# motor_driver.net
KiCad netlist of a schematic drawn in Altium Designer
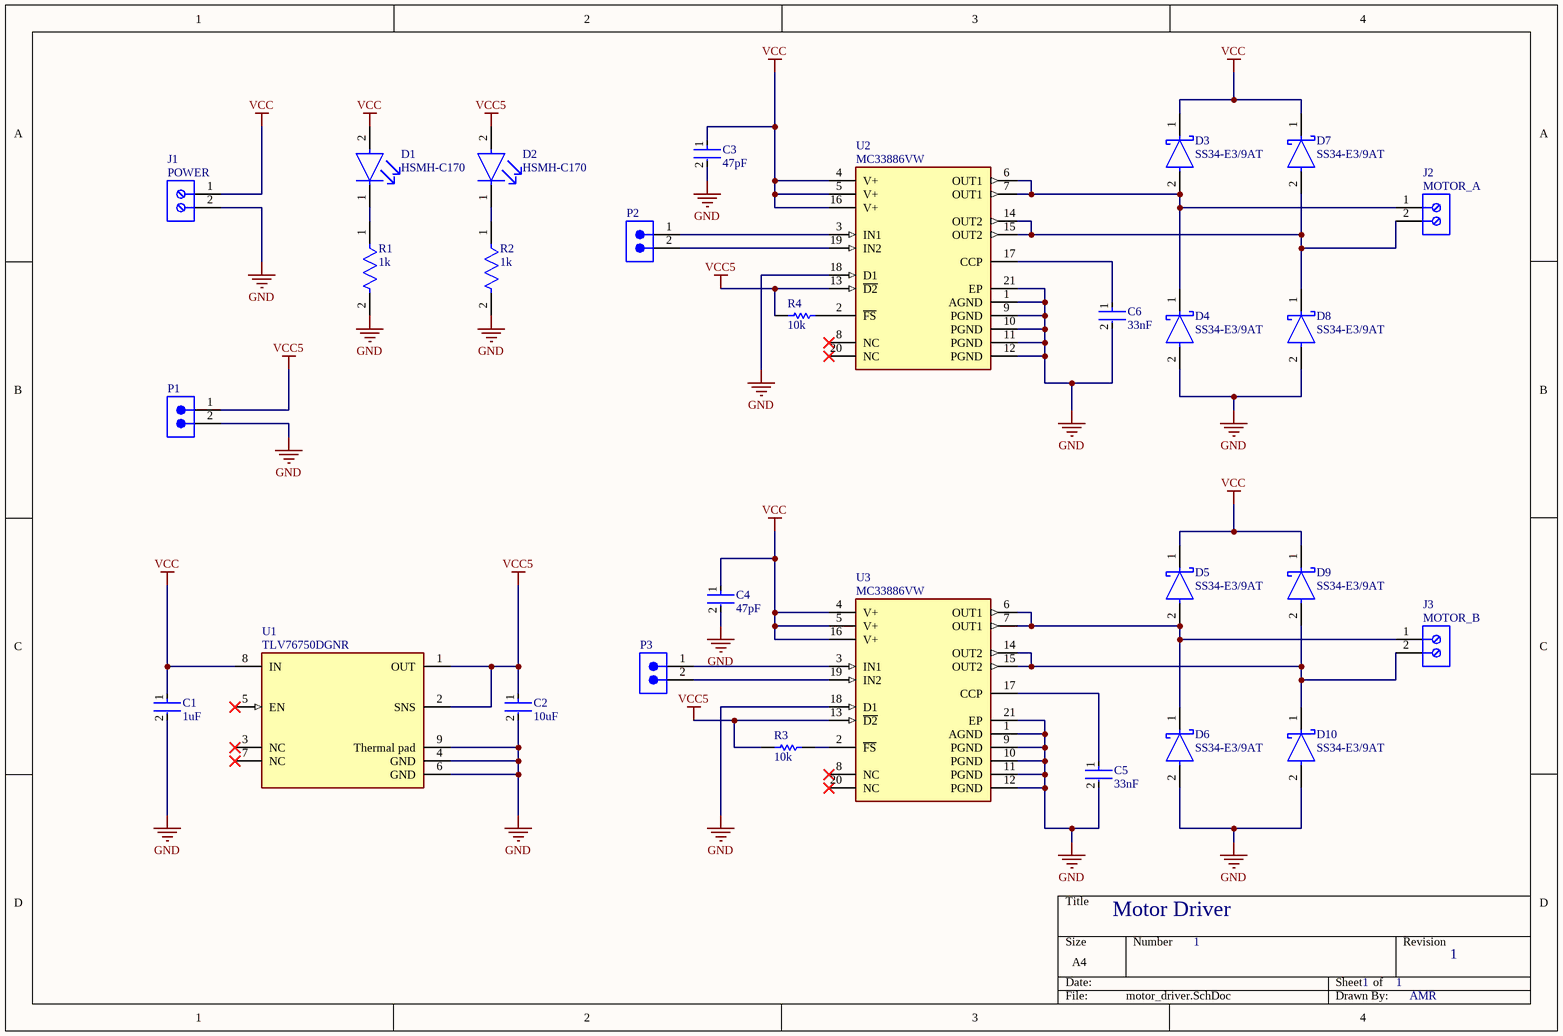
[diagram p0: motor_driver.SchDoc]

(export (version "E")
  (design (tool "Eeschema 10.0.6"))
  (components
    (comp (ref "C1")
      (value "1uF")
      (footprint "FP-CC0603-DA-IPC_A")
      (description "CAP CER 0.1UF 16V X7R 0603")
      (fields
        (field (name "OCTOPART") "https://octopart.com/cc0603krx7r7bb104-yageo-192941")
        (field (name "TOLERANCE") "0.1")
      )
      (libsource (lib "1uF") (part "CMP-2000-05002-2"))
    )
    (comp (ref "C2")
      (value "10uF")
      (footprint "FP-GRM188-0_1-e0_2_0_55-IPC_A")
      (description "Chip Multilayer Ceramic Capacitors for General Purpose, 0603, 10uF, X5R, 15%, 20%, 6.3V")
      (fields (field (name "VOLTAGE") "6.3V") (field (name "TOLERANCE") "20%"))
      (libsource (lib "Altium Content Vault") (part "02cd4be3c70576c341d710602a673aa"))
    )
    (comp (ref "C3")
      (value "47pF")
      (footprint "FP-C0805C-DN-IPC_A")
      (description "CAP CER 47PF 100V 5% NP0 0805")
      (fields
        (field (name "MANUFACTURER") "KEMET")
        (field (name "OCTOPART") "https://octopart.com/c0805c470j1gactu-kemet-9138638")
      )
      (libsource (lib "Altium Content Vault") (part "b4654b650e69147ec39a6b967a45e02"))
    )
    (comp (ref "C4")
      (value "47pF")
      (footprint "FP-C0805C-DN-IPC_A")
      (description "CAP CER 47PF 100V 5% NP0 0805")
      (fields
        (field (name "MANUFACTURER") "KEMET")
        (field (name "OCTOPART") "https://octopart.com/c0805c470j1gactu-kemet-9138638")
      )
      (libsource (lib "Altium Content Vault") (part "b4654b650e69147ec39a6b967a45e02"))
    )
    (comp (ref "C5")
      (value "33nF")
      (footprint "FP-CC0805-0_85-MFG")
      (description "CAP CER 0.033UF 25V X7R 0805")
      (fields
        (field (name "MANUFACTURER PART NUMBER") "CC0805KRX7R8BB333")
        (field (name "MANUFACTURER") "Yageo")
      )
      (libsource (lib "Altium Content Vault") (part "11868f565c42a9108669ba33697ecf6"))
    )
    (comp (ref "C6")
      (value "33nF")
      (footprint "FP-CC0805-0_85-MFG")
      (description "CAP CER 0.033UF 25V X7R 0805")
      (fields
        (field (name "MANUFACTURER PART NUMBER") "CC0805KRX7R8BB333")
        (field (name "MANUFACTURER") "Yageo")
      )
      (libsource (lib "Altium Content Vault") (part "11868f565c42a9108669ba33697ecf6"))
    )
    (comp (ref "D1")
      (value "HSMH-C170")
      (footprint "FP-HSMS-C170-MFG")
      (description "LED RED DIFFUSED CHIP SMD")
      (libsource (lib "Altium Content Vault") (part "8706943c75ba83719d021d2fdc84c58"))
    )
    (comp (ref "D2")
      (value "HSMH-C170")
      (footprint "FP-HSMS-C170-MFG")
      (description "LED RED DIFFUSED CHIP SMD")
      (libsource (lib "Altium Content Vault") (part "8706943c75ba83719d021d2fdc84c58"))
    )
    (comp (ref "D3")
      (value "SS34-E3/9AT")
      (footprint "FP-SMC-MFG")
      (description "DIODE SCHOTTKY 40V 3A DO214AB")
      (libsource (lib "Altium Content Vault") (part "c1678fac7984e62e0809fbf79c06691"))
    )
    (comp (ref "D4")
      (value "SS34-E3/9AT")
      (footprint "FP-SMC-MFG")
      (description "DIODE SCHOTTKY 40V 3A DO214AB")
      (libsource (lib "Altium Content Vault") (part "c1678fac7984e62e0809fbf79c06691"))
    )
    (comp (ref "D5")
      (value "SS34-E3/9AT")
      (footprint "FP-SMC-MFG")
      (description "DIODE SCHOTTKY 40V 3A DO214AB")
      (libsource (lib "Altium Content Vault") (part "c1678fac7984e62e0809fbf79c06691"))
    )
    (comp (ref "D6")
      (value "SS34-E3/9AT")
      (footprint "FP-SMC-MFG")
      (description "DIODE SCHOTTKY 40V 3A DO214AB")
      (libsource (lib "Altium Content Vault") (part "c1678fac7984e62e0809fbf79c06691"))
    )
    (comp (ref "D7")
      (value "SS34-E3/9AT")
      (footprint "FP-SMC-MFG")
      (description "DIODE SCHOTTKY 40V 3A DO214AB")
      (libsource (lib "Altium Content Vault") (part "c1678fac7984e62e0809fbf79c06691"))
    )
    (comp (ref "D8")
      (value "SS34-E3/9AT")
      (footprint "FP-SMC-MFG")
      (description "DIODE SCHOTTKY 40V 3A DO214AB")
      (libsource (lib "Altium Content Vault") (part "c1678fac7984e62e0809fbf79c06691"))
    )
    (comp (ref "D9")
      (value "SS34-E3/9AT")
      (footprint "FP-SMC-MFG")
      (description "DIODE SCHOTTKY 40V 3A DO214AB")
      (libsource (lib "Altium Content Vault") (part "c1678fac7984e62e0809fbf79c06691"))
    )
    (comp (ref "D10")
      (value "SS34-E3/9AT")
      (footprint "FP-SMC-MFG")
      (description "DIODE SCHOTTKY 40V 3A DO214AB")
      (libsource (lib "Altium Content Vault") (part "c1678fac7984e62e0809fbf79c06691"))
    )
    (comp (ref "J1")
      (value "POWER")
      (footprint "691103110002")
      (fields (field (name "VOLTAGE") "125V"))
      (libsource (lib "Altium Content Vault") (part "TBL - 1R - 02P - Screw"))
    )
    (comp (ref "J2")
      (value "MOTOR_A")
      (footprint "691103110002")
      (fields (field (name "VOLTAGE") "125V"))
      (libsource (lib "Altium Content Vault") (part "TBL - 1R - 02P - Screw"))
    )
    (comp (ref "J3")
      (value "MOTOR_B")
      (footprint "691103110002")
      (fields (field (name "VOLTAGE") "125V"))
      (libsource (lib "Altium Content Vault") (part "TBL - 1R - 02P - Screw"))
    )
    (comp (ref "P1")
      (value "61300211121")
      (footprint "61300211121")
      (libsource (lib "Altium Content Vault") (part "Header_Male_1R_02P"))
    )
    (comp (ref "P2")
      (value "61300211121")
      (footprint "61300211121")
      (libsource (lib "Altium Content Vault") (part "Header_Male_1R_02P"))
    )
    (comp (ref "P3")
      (value "61300211121")
      (footprint "61300211121")
      (libsource (lib "Altium Content Vault") (part "Header_Male_1R_02P"))
    )
    (comp (ref "R1")
      (value "1k")
      (footprint "FP-RC0603-0_55-IPC_B")
      (description "RES 1K OHM 1% 1/10W 0603")
      (fields (field (name "TOLERANCE") "1%"))
      (libsource (lib "Components - 03.07.23 - 14.28") (part "CMP-1659-00009-5"))
    )
    (comp (ref "R2")
      (value "1k")
      (footprint "FP-RC0603-0_55-IPC_B")
      (description "RES 1K OHM 1% 1/10W 0603")
      (fields (field (name "TOLERANCE") "1%"))
      (libsource (lib "Components - 03.07.23 - 14.28") (part "CMP-1659-00009-5"))
    )
    (comp (ref "R3")
      (value "10k")
      (footprint "RESC1609X50X30ML8T20")
      (description "Chip Resistor, 10 KOhm, +/- 1%, 100 mW, -55 to 155 degC, 0603 (1608 Metric), RoHS, Tape and Reel")
      (fields (field (name "MANUFACTURER") "Vishay Semiconductor"))
      (libsource (lib "Altium Content Vault") (part "RES-2"))
    )
    (comp (ref "R4")
      (value "10k")
      (footprint "RESC1609X50X30ML8T20")
      (description "Chip Resistor, 10 KOhm, +/- 1%, 100 mW, -55 to 155 degC, 0603 (1608 Metric), RoHS, Tape and Reel")
      (fields (field (name "MANUFACTURER") "Vishay Semiconductor"))
      (libsource (lib "Altium Content Vault") (part "RES-2"))
    )
    (comp (ref "U1")
      (value "TLV76750DGNR")
      (footprint "FP-DGN0008G-IPC_A")
      (libsource (lib "Altium Content Vault") (part "4137fefd6f2351a27154aa09bf60b26"))
    )
    (comp (ref "U2")
      (value "MC33886VW")
      (footprint "FP-SOT397-2-IPC_A")
      (description "Motor Driver CMOS Parallel 20-HSOP")
      (libsource (lib "Altium Content Vault") (part "637c7454df18ad6f63f2a5204066dbd"))
    )
    (comp (ref "U3")
      (value "MC33886VW")
      (footprint "FP-SOT397-2-IPC_A")
      (description "Motor Driver CMOS Parallel 20-HSOP")
      (libsource (lib "Altium Content Vault") (part "637c7454df18ad6f63f2a5204066dbd"))
    )
  )
  (nets
    (net (code "1") (name "GND") (class "Default")
      (node (ref "C1") (pin "2") (pinfunction "2_2") (pintype "passive"))
      (node (ref "C2") (pin "2") (pinfunction "2_2") (pintype "passive"))
      (node (ref "C3") (pin "2") (pinfunction "2_2") (pintype "passive"))
      (node (ref "C4") (pin "2") (pinfunction "2_2") (pintype "passive"))
      (node (ref "C5") (pin "2") (pinfunction "2_2") (pintype "passive"))
      (node (ref "C6") (pin "2") (pinfunction "2_2") (pintype "passive"))
      (node (ref "D10") (pin "2") (pinfunction "A_2") (pintype "passive"))
      (node (ref "D4") (pin "2") (pinfunction "A_2") (pintype "passive"))
      (node (ref "D6") (pin "2") (pinfunction "A_2") (pintype "passive"))
      (node (ref "D8") (pin "2") (pinfunction "A_2") (pintype "passive"))
      (node (ref "J1") (pin "2") (pinfunction "2_2") (pintype "passive"))
      (node (ref "P1") (pin "2") (pinfunction "2_2") (pintype "passive"))
      (node (ref "R1") (pin "2") (pinfunction "2_2") (pintype "passive"))
      (node (ref "R2") (pin "2") (pinfunction "2_2") (pintype "passive"))
      (node (ref "U1") (pin "4") (pinfunction "GND_4") (pintype "power_in"))
      (node (ref "U1") (pin "6") (pinfunction "GND_6") (pintype "power_in"))
      (node (ref "U1") (pin "9") (pinfunction "Thermal_pad_9") (pintype "power_in"))
      (node (ref "U2") (pin "1") (pinfunction "AGND_1") (pintype "power_in"))
      (node (ref "U2") (pin "10") (pinfunction "PGND_10") (pintype "power_in"))
      (node (ref "U2") (pin "11") (pinfunction "PGND_11") (pintype "power_in"))
      (node (ref "U2") (pin "12") (pinfunction "PGND_12") (pintype "power_in"))
      (node (ref "U2") (pin "18") (pinfunction "D1_18") (pintype "input"))
      (node (ref "U2") (pin "21") (pinfunction "EP_21") (pintype "passive"))
      (node (ref "U2") (pin "9") (pinfunction "PGND_9") (pintype "power_in"))
      (node (ref "U3") (pin "1") (pinfunction "AGND_1") (pintype "power_in"))
      (node (ref "U3") (pin "10") (pinfunction "PGND_10") (pintype "power_in"))
      (node (ref "U3") (pin "11") (pinfunction "PGND_11") (pintype "power_in"))
      (node (ref "U3") (pin "12") (pinfunction "PGND_12") (pintype "power_in"))
      (node (ref "U3") (pin "18") (pinfunction "D1_18") (pintype "input"))
      (node (ref "U3") (pin "21") (pinfunction "EP_21") (pintype "passive"))
      (node (ref "U3") (pin "9") (pinfunction "PGND_9") (pintype "power_in"))
    )
    (net (code "2") (name "Net-(D1-C)") (class "Default")
      (node (ref "D1") (pin "1") (pinfunction "C_1") (pintype "passive"))
      (node (ref "R1") (pin "1") (pinfunction "1_1") (pintype "passive"))
    )
    (net (code "3") (name "Net-(D2-C)") (class "Default")
      (node (ref "D2") (pin "1") (pinfunction "C_1") (pintype "passive"))
      (node (ref "R2") (pin "1") (pinfunction "1_1") (pintype "passive"))
    )
    (net (code "4") (name "Net-(D3-A)") (class "Default")
      (node (ref "D3") (pin "2") (pinfunction "A_2") (pintype "passive"))
      (node (ref "D4") (pin "1") (pinfunction "C_1") (pintype "passive"))
      (node (ref "J2") (pin "1") (pinfunction "1_1") (pintype "passive"))
      (node (ref "U2") (pin "6") (pinfunction "OUT1_6") (pintype "output"))
      (node (ref "U2") (pin "7") (pinfunction "OUT1_7") (pintype "output"))
    )
    (net (code "5") (name "Net-(D5-A)") (class "Default")
      (node (ref "D5") (pin "2") (pinfunction "A_2") (pintype "passive"))
      (node (ref "D6") (pin "1") (pinfunction "C_1") (pintype "passive"))
      (node (ref "J3") (pin "1") (pinfunction "1_1") (pintype "passive"))
      (node (ref "U3") (pin "6") (pinfunction "OUT1_6") (pintype "output"))
      (node (ref "U3") (pin "7") (pinfunction "OUT1_7") (pintype "output"))
    )
    (net (code "6") (name "Net-(D7-A)") (class "Default")
      (node (ref "D7") (pin "2") (pinfunction "A_2") (pintype "passive"))
      (node (ref "D8") (pin "1") (pinfunction "C_1") (pintype "passive"))
      (node (ref "J2") (pin "2") (pinfunction "2_2") (pintype "passive"))
      (node (ref "U2") (pin "14") (pinfunction "OUT2_14") (pintype "output"))
      (node (ref "U2") (pin "15") (pinfunction "OUT2_15") (pintype "output"))
    )
    (net (code "7") (name "Net-(D10-C)") (class "Default")
      (node (ref "D10") (pin "1") (pinfunction "C_1") (pintype "passive"))
      (node (ref "D9") (pin "2") (pinfunction "A_2") (pintype "passive"))
      (node (ref "J3") (pin "2") (pinfunction "2_2") (pintype "passive"))
      (node (ref "U3") (pin "14") (pinfunction "OUT2_14") (pintype "output"))
      (node (ref "U3") (pin "15") (pinfunction "OUT2_15") (pintype "output"))
    )
    (net (code "8") (name "Net-(U2-CCP)") (class "Default")
      (node (ref "C6") (pin "1") (pinfunction "1_1") (pintype "passive"))
      (node (ref "U2") (pin "17") (pinfunction "CCP_17") (pintype "passive"))
    )
    (net (code "9") (name "Net-(U2-IN1)") (class "Default")
      (node (ref "P2") (pin "1") (pinfunction "1_1") (pintype "passive"))
      (node (ref "U2") (pin "3") (pinfunction "IN1_3") (pintype "input"))
    )
    (net (code "10") (name "Net-(U2-IN2)") (class "Default")
      (node (ref "P2") (pin "2") (pinfunction "2_2") (pintype "passive"))
      (node (ref "U2") (pin "19") (pinfunction "IN2_19") (pintype "input"))
    )
    (net (code "11") (name "Net-(U2-~{FS})") (class "Default")
      (node (ref "R4") (pin "2") (pinfunction "2_2") (pintype "passive"))
      (node (ref "U2") (pin "2") (pinfunction "~{FS}_2") (pintype "open_collector"))
    )
    (net (code "12") (name "Net-(U3-CCP)") (class "Default")
      (node (ref "C5") (pin "1") (pinfunction "1_1") (pintype "passive"))
      (node (ref "U3") (pin "17") (pinfunction "CCP_17") (pintype "passive"))
    )
    (net (code "13") (name "Net-(U3-IN1)") (class "Default")
      (node (ref "P3") (pin "1") (pinfunction "1_1") (pintype "passive"))
      (node (ref "U3") (pin "3") (pinfunction "IN1_3") (pintype "input"))
    )
    (net (code "14") (name "Net-(U3-IN2)") (class "Default")
      (node (ref "P3") (pin "2") (pinfunction "2_2") (pintype "passive"))
      (node (ref "U3") (pin "19") (pinfunction "IN2_19") (pintype "input"))
    )
    (net (code "15") (name "Net-(U3-~{FS})") (class "Default")
      (node (ref "R3") (pin "2") (pinfunction "2_2") (pintype "passive"))
      (node (ref "U3") (pin "2") (pinfunction "~{FS}_2") (pintype "open_collector"))
    )
    (net (code "16") (name "VCC") (class "Default")
      (node (ref "C1") (pin "1") (pinfunction "1_1") (pintype "passive"))
      (node (ref "C3") (pin "1") (pinfunction "1_1") (pintype "passive"))
      (node (ref "C4") (pin "1") (pinfunction "1_1") (pintype "passive"))
      (node (ref "D1") (pin "2") (pinfunction "A_2") (pintype "passive"))
      (node (ref "D3") (pin "1") (pinfunction "C_1") (pintype "passive"))
      (node (ref "D5") (pin "1") (pinfunction "C_1") (pintype "passive"))
      (node (ref "D7") (pin "1") (pinfunction "C_1") (pintype "passive"))
      (node (ref "D9") (pin "1") (pinfunction "C_1") (pintype "passive"))
      (node (ref "J1") (pin "1") (pinfunction "1_1") (pintype "passive"))
      (node (ref "U1") (pin "8") (pinfunction "IN_8") (pintype "power_in"))
      (node (ref "U2") (pin "16") (pinfunction "V+_16") (pintype "power_in"))
      (node (ref "U2") (pin "4") (pinfunction "V+_4") (pintype "power_in"))
      (node (ref "U2") (pin "5") (pinfunction "V+_5") (pintype "power_in"))
      (node (ref "U3") (pin "16") (pinfunction "V+_16") (pintype "power_in"))
      (node (ref "U3") (pin "4") (pinfunction "V+_4") (pintype "power_in"))
      (node (ref "U3") (pin "5") (pinfunction "V+_5") (pintype "power_in"))
    )
    (net (code "17") (name "VCC5") (class "Default")
      (node (ref "C2") (pin "1") (pinfunction "1_1") (pintype "passive"))
      (node (ref "D2") (pin "2") (pinfunction "A_2") (pintype "passive"))
      (node (ref "P1") (pin "1") (pinfunction "1_1") (pintype "passive"))
      (node (ref "R3") (pin "1") (pinfunction "1_1") (pintype "passive"))
      (node (ref "R4") (pin "1") (pinfunction "1_1") (pintype "passive"))
      (node (ref "U1") (pin "1") (pinfunction "OUT_1") (pintype "passive"))
      (node (ref "U1") (pin "2") (pinfunction "SNS_2") (pintype "passive"))
      (node (ref "U2") (pin "13") (pinfunction "~{D2}_13") (pintype "input"))
      (node (ref "U3") (pin "13") (pinfunction "~{D2}_13") (pintype "input"))
    )
    (net (code "18") (name "unconnected-(U1-EN-Pad5)") (class "Default")
      (node (ref "U1") (pin "5") (pinfunction "EN_5") (pintype "input+no_connect"))
    )
    (net (code "19") (name "unconnected-(U1-NC-Pad3)") (class "Default")
      (node (ref "U1") (pin "3") (pinfunction "NC_3") (pintype "passive+no_connect"))
    )
    (net (code "20") (name "unconnected-(U1-NC-Pad7)") (class "Default")
      (node (ref "U1") (pin "7") (pinfunction "NC_7") (pintype "passive+no_connect"))
    )
    (net (code "21") (name "unconnected-(U2-NC-Pad8)") (class "Default")
      (node (ref "U2") (pin "8") (pinfunction "NC_8") (pintype "passive+no_connect"))
    )
    (net (code "22") (name "unconnected-(U2-NC-Pad20)") (class "Default")
      (node (ref "U2") (pin "20") (pinfunction "NC_20") (pintype "passive+no_connect"))
    )
    (net (code "23") (name "unconnected-(U3-NC-Pad8)") (class "Default")
      (node (ref "U3") (pin "8") (pinfunction "NC_8") (pintype "passive+no_connect"))
    )
    (net (code "24") (name "unconnected-(U3-NC-Pad20)") (class "Default")
      (node (ref "U3") (pin "20") (pinfunction "NC_20") (pintype "passive+no_connect"))
    )
  )
)
